# SaLEasyMag.net
KiCad netlist of a schematic drawn in EAGLE
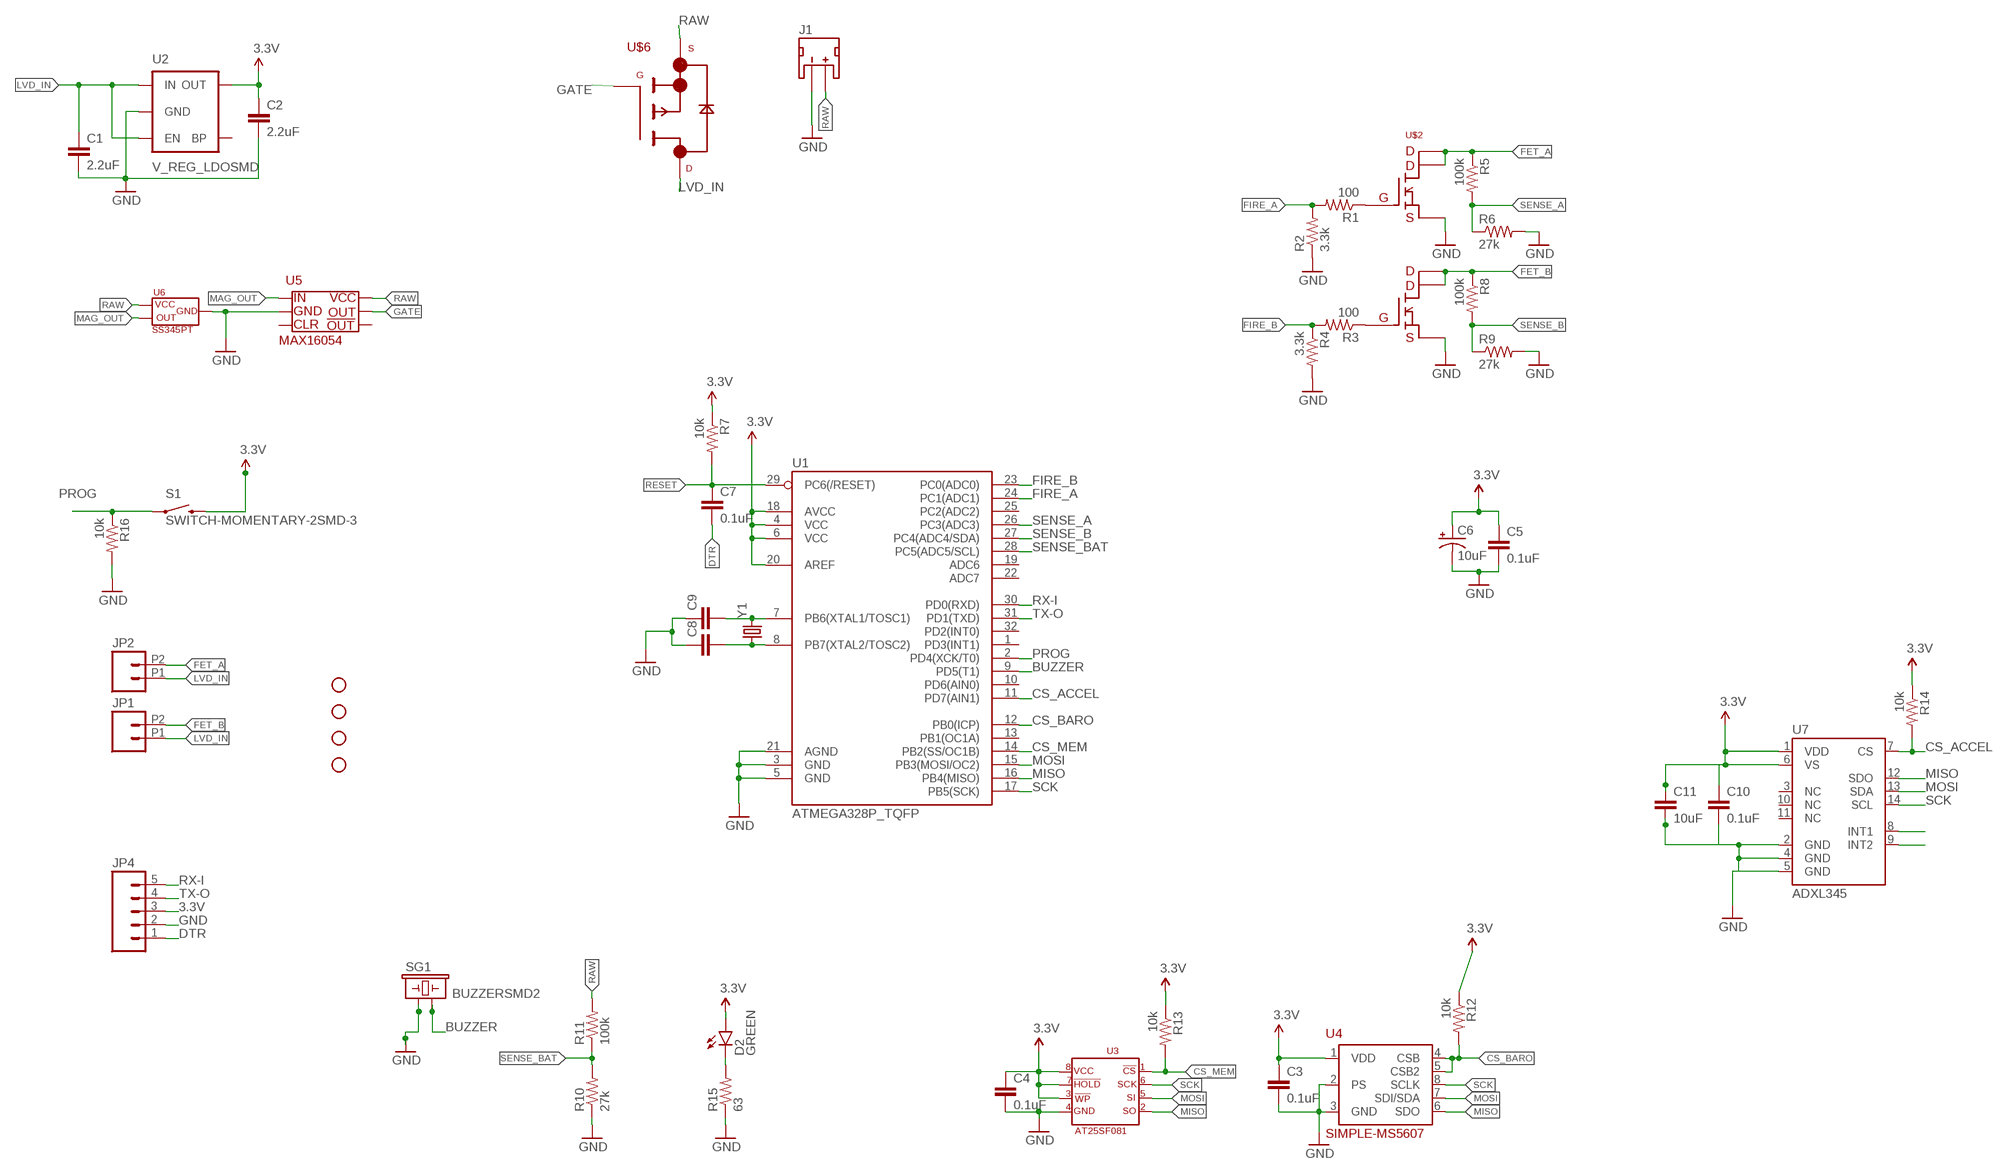
[diagram p0: schematic, sheet 1]

(export (version "E")
  (design (tool "Eeschema 10.0.6"))
  (components
    (comp (ref "C1")
      (value "2.2uF")
      (footprint "eagle-import:0603-CAP")
      (libsource (lib "eagle-import") (part "SparkFun-Passives_CAP0603-CAP"))
    )
    (comp (ref "C2")
      (value "2.2uF")
      (footprint "eagle-import:0603-CAP")
      (libsource (lib "eagle-import") (part "SparkFun-Passives_CAP0603-CAP"))
    )
    (comp (ref "C3")
      (value "0.1uF")
      (footprint "eagle-import:0603-CAP")
      (libsource (lib "eagle-import") (part "SparkFun-Passives_CAP0603-CAP"))
    )
    (comp (ref "C4")
      (value "0.1uF")
      (footprint "eagle-import:0603-CAP")
      (libsource (lib "eagle-import") (part "SparkFun-Passives_CAP0603-CAP"))
    )
    (comp (ref "C5")
      (value "0.1uF")
      (footprint "eagle-import:0603-CAP")
      (libsource (lib "eagle-import") (part "SparkFun-Passives_CAP0603-CAP"))
    )
    (comp (ref "C6")
      (value "10uF")
      (footprint "eagle-import:EIA3216")
      (libsource (lib "eagle-import") (part "CAP_POL1206"))
    )
    (comp (ref "C7")
      (value "0.1uF")
      (footprint "eagle-import:0603-CAP")
      (libsource (lib "eagle-import") (part "SparkFun-Passives_CAP0603-CAP"))
    )
    (comp (ref "C8")
      (value "CAP0402-CAP")
      (footprint "eagle-import:0402-CAP")
      (libsource (lib "eagle-import") (part "CAP0402-CAP"))
    )
    (comp (ref "C9")
      (value "CAP0402-CAP")
      (footprint "eagle-import:0402-CAP")
      (libsource (lib "eagle-import") (part "CAP0402-CAP"))
    )
    (comp (ref "C10")
      (value "0.1uF")
      (footprint "eagle-import:0603-CAP")
      (libsource (lib "eagle-import") (part "SparkFun-Passives_CAP0603-CAP"))
    )
    (comp (ref "C11")
      (value "10uF")
      (footprint "eagle-import:0603-CAP")
      (libsource (lib "eagle-import") (part "SparkFun-Passives_CAP0603-CAP"))
    )
    (comp (ref "D2")
      (value "GREEN")
      (footprint "eagle-import:LED-1206")
      (libsource (lib "eagle-import") (part "LED-GREENLARGE"))
    )
    (comp (ref "J1")
      (value "JST_2MM_MALE")
      (footprint "eagle-import:JST-2-SMD")
      (libsource (lib "eagle-import") (part "JST_2MM_MALE"))
    )
    (comp (ref "JP1")
      (value "M022.54MM_SCREWTERM")
      (footprint "eagle-import:1X02_2.54_SCREWTERM")
      (libsource (lib "eagle-import") (part "M022.54MM_SCREWTERM"))
    )
    (comp (ref "JP2")
      (value "M022.54MM_SCREWTERM")
      (footprint "eagle-import:1X02_2.54_SCREWTERM")
      (libsource (lib "eagle-import") (part "M022.54MM_SCREWTERM"))
    )
    (comp (ref "JP4")
      (value "M05SMD")
      (footprint "eagle-import:1X05-1MM")
      (libsource (lib "eagle-import") (part "M05SMD"))
    )
    (comp (ref "R1")
      (value "100")
      (footprint "eagle-import:0603-RES")
      (libsource (lib "eagle-import") (part "RESISTOR0603-RES"))
    )
    (comp (ref "R2")
      (value "3.3k")
      (footprint "eagle-import:0603-RES")
      (libsource (lib "eagle-import") (part "RESISTOR0603-RES"))
    )
    (comp (ref "R3")
      (value "100")
      (footprint "eagle-import:0603-RES")
      (libsource (lib "eagle-import") (part "RESISTOR0603-RES"))
    )
    (comp (ref "R4")
      (value "3.3k")
      (footprint "eagle-import:0603-RES")
      (libsource (lib "eagle-import") (part "RESISTOR0603-RES"))
    )
    (comp (ref "R5")
      (value "100k")
      (footprint "eagle-import:0603-RES")
      (libsource (lib "eagle-import") (part "RESISTOR0603-RES"))
    )
    (comp (ref "R6")
      (value "27k")
      (footprint "eagle-import:0603-RES")
      (libsource (lib "eagle-import") (part "RESISTOR0603-RES"))
    )
    (comp (ref "R7")
      (value "10k")
      (footprint "eagle-import:0603-RES")
      (libsource (lib "eagle-import") (part "RESISTOR0603-RES"))
    )
    (comp (ref "R8")
      (value "100k")
      (footprint "eagle-import:0603-RES")
      (libsource (lib "eagle-import") (part "RESISTOR0603-RES"))
    )
    (comp (ref "R9")
      (value "27k")
      (footprint "eagle-import:0603-RES")
      (libsource (lib "eagle-import") (part "RESISTOR0603-RES"))
    )
    (comp (ref "R10")
      (value "27k")
      (footprint "eagle-import:0603-RES")
      (libsource (lib "eagle-import") (part "RESISTOR0603-RES"))
    )
    (comp (ref "R11")
      (value "100k")
      (footprint "eagle-import:0603-RES")
      (libsource (lib "eagle-import") (part "RESISTOR0603-RES"))
    )
    (comp (ref "R12")
      (value "10k")
      (footprint "eagle-import:0603-RES")
      (libsource (lib "eagle-import") (part "RESISTOR0603-RES"))
    )
    (comp (ref "R13")
      (value "10k")
      (footprint "eagle-import:0603-RES")
      (libsource (lib "eagle-import") (part "RESISTOR0603-RES"))
    )
    (comp (ref "R14")
      (value "10k")
      (footprint "eagle-import:0603-RES")
      (libsource (lib "eagle-import") (part "RESISTOR0603-RES"))
    )
    (comp (ref "R15")
      (value "63")
      (footprint "eagle-import:0603-RES")
      (libsource (lib "eagle-import") (part "RESISTOR0603-RES"))
    )
    (comp (ref "R16")
      (value "10k")
      (footprint "eagle-import:0603-RES")
      (libsource (lib "eagle-import") (part "RESISTOR0603-RES"))
    )
    (comp (ref "S1")
      (value "SWITCH-MOMENTARY-2SMD-3")
      (footprint "eagle-import:TACTILE_SWITCH_SMD-3")
      (libsource (lib "eagle-import") (part "SWITCH-MOMENTARY-2SMD-3"))
    )
    (comp (ref "SG1")
      (value "BUZZERSMD2")
      (footprint "eagle-import:BUZZER-CCV")
      (libsource (lib "eagle-import") (part "BUZZERSMD2"))
    )
    (comp (ref "STANDOFF1")
      (value "STAND-OFF")
      (footprint "eagle-import:STAND-OFF")
      (libsource (lib "eagle-import") (part "STAND-OFF"))
    )
    (comp (ref "STANDOFF2")
      (value "STAND-OFF")
      (footprint "eagle-import:STAND-OFF")
      (libsource (lib "eagle-import") (part "STAND-OFF"))
    )
    (comp (ref "STANDOFF3")
      (value "STAND-OFF")
      (footprint "eagle-import:STAND-OFF")
      (libsource (lib "eagle-import") (part "STAND-OFF"))
    )
    (comp (ref "STANDOFF4")
      (value "STAND-OFF")
      (footprint "eagle-import:STAND-OFF")
      (libsource (lib "eagle-import") (part "STAND-OFF"))
    )
    (comp (ref "U$2")
      (value "SI7232DN")
      (footprint "eagle-import:SI7232DN")
      (libsource (lib "eagle-import") (part "SI7232DN"))
    )
    (comp (ref "U$6")
      (value "SI7615ADN")
      (footprint "eagle-import:SI7615ADN")
      (libsource (lib "eagle-import") (part "SI7615ADN"))
    )
    (comp (ref "U1")
      (value "ATMEGA328P_TQFP")
      (footprint "eagle-import:TQFP32-08")
      (libsource (lib "eagle-import") (part "ATMEGA328P_TQFP"))
    )
    (comp (ref "U2")
      (value "V_REG_LDOSMD")
      (footprint "eagle-import:SOT23-5")
      (libsource (lib "eagle-import") (part "V_REG_LDOSMD"))
    )
    (comp (ref "U3")
      (value "AT25SF081")
      (footprint "eagle-import:AT25SF081")
      (libsource (lib "eagle-import") (part "AT25SF081"))
    )
    (comp (ref "U4")
      (value "SIMPLE-MS5607")
      (footprint "eagle-import:MS5607")
      (libsource (lib "eagle-import") (part "SIMPLE-MS5607"))
    )
    (comp (ref "U5")
      (value "MAX16054")
      (footprint "eagle-import:MAX16054")
      (libsource (lib "eagle-import") (part "MAX16054"))
    )
    (comp (ref "U6")
      (value "SS345PT")
      (footprint "eagle-import:SS345PT")
      (libsource (lib "eagle-import") (part "SS345PT"))
    )
    (comp (ref "U7")
      (value "ADXL345")
      (footprint "eagle-import:LGA14")
      (libsource (lib "eagle-import") (part "ADXL345"))
    )
    (comp (ref "Y1")
      (value "CRYSTAL5X3")
      (footprint "eagle-import:CRYSTAL-SMD-5X3")
      (libsource (lib "eagle-import") (part "CRYSTAL5X3"))
    )
  )
  (nets
    (net (code "1") (name "/BUZZER") (class "Default")
      (node (ref "SG1") (pin "-") (pinfunction "2_-") (pintype "passive"))
      (node (ref "U1") (pin "9") (pinfunction "PD5(T1)_9") (pintype "bidirectional"))
    )
    (net (code "2") (name "/CS_ACCEL") (class "Default")
      (node (ref "R14") (pin "2") (pinfunction "2_2") (pintype "passive"))
      (node (ref "U1") (pin "11") (pinfunction "PD7(AIN1)_11") (pintype "bidirectional"))
      (node (ref "U7") (pin "7") (pinfunction "CS_7") (pintype "bidirectional"))
    )
    (net (code "3") (name "/PROG") (class "Default")
      (node (ref "R16") (pin "1") (pinfunction "1_1") (pintype "passive"))
      (node (ref "S1") (pin "1") (pinfunction "1_1") (pintype "passive"))
      (node (ref "U1") (pin "2") (pinfunction "PD4(XCK/T0)_2") (pintype "bidirectional"))
    )
    (net (code "4") (name "/RX-I") (class "Default")
      (node (ref "JP4") (pin "5") (pinfunction "5_5") (pintype "passive"))
      (node (ref "U1") (pin "30") (pinfunction "PD0(RXD)_30") (pintype "bidirectional"))
    )
    (net (code "5") (name "/TX-O") (class "Default")
      (node (ref "JP4") (pin "4") (pinfunction "4_4") (pintype "passive"))
      (node (ref "U1") (pin "31") (pinfunction "PD1(TXD)_31") (pintype "bidirectional"))
    )
    (net (code "6") (name "3.3V") (class "Default")
      (node (ref "C10") (pin "1") (pinfunction "1_1") (pintype "passive"))
      (node (ref "C11") (pin "1") (pinfunction "1_1") (pintype "passive"))
      (node (ref "C2") (pin "1") (pinfunction "1_1") (pintype "passive"))
      (node (ref "C3") (pin "1") (pinfunction "1_1") (pintype "passive"))
      (node (ref "C4") (pin "1") (pinfunction "1_1") (pintype "passive"))
      (node (ref "C5") (pin "1") (pinfunction "1_1") (pintype "passive"))
      (node (ref "C6") (pin "A") (pinfunction "+_A") (pintype "passive"))
      (node (ref "D2") (pin "A") (pinfunction "A_A") (pintype "passive"))
      (node (ref "JP4") (pin "3") (pinfunction "3_3") (pintype "passive"))
      (node (ref "R12") (pin "1") (pinfunction "1_1") (pintype "passive"))
      (node (ref "R13") (pin "1") (pinfunction "1_1") (pintype "passive"))
      (node (ref "R14") (pin "1") (pinfunction "1_1") (pintype "passive"))
      (node (ref "R7") (pin "1") (pinfunction "1_1") (pintype "passive"))
      (node (ref "S1") (pin "4") (pinfunction "2_4") (pintype "passive"))
      (node (ref "U1") (pin "18") (pinfunction "AVCC_18") (pintype "bidirectional"))
      (node (ref "U1") (pin "20") (pinfunction "AREF_20") (pintype "bidirectional"))
      (node (ref "U1") (pin "4") (pinfunction "VCC_4") (pintype "bidirectional"))
      (node (ref "U1") (pin "6") (pinfunction "VCC_6") (pintype "bidirectional"))
      (node (ref "U2") (pin "5") (pinfunction "OUT_5") (pintype "passive"))
      (node (ref "U3") (pin "!HOLD") (pinfunction "~{HOLD}_!HOLD") (pintype "bidirectional"))
      (node (ref "U3") (pin "!WP") (pinfunction "~{WP}_!WP") (pintype "bidirectional"))
      (node (ref "U3") (pin "VCC") (pinfunction "VCC_VCC") (pintype "bidirectional"))
      (node (ref "U4") (pin "1") (pinfunction "VDD_1") (pintype "bidirectional"))
      (node (ref "U7") (pin "1") (pinfunction "VDD_1") (pintype "bidirectional"))
      (node (ref "U7") (pin "6") (pinfunction "VS_6") (pintype "bidirectional"))
    )
    (net (code "7") (name "CS_BARO") (class "Default")
      (node (ref "R12") (pin "2") (pinfunction "2_2") (pintype "passive"))
      (node (ref "U1") (pin "12") (pinfunction "PB0(ICP)_12") (pintype "bidirectional"))
      (node (ref "U4") (pin "4") (pinfunction "CSB_4") (pintype "bidirectional"))
      (node (ref "U4") (pin "5") (pinfunction "CSB2_5") (pintype "bidirectional"))
    )
    (net (code "8") (name "CS_MEM") (class "Default")
      (node (ref "R13") (pin "2") (pinfunction "2_2") (pintype "passive"))
      (node (ref "U1") (pin "14") (pinfunction "PB2(SS/OC1B)_14") (pintype "bidirectional"))
      (node (ref "U3") (pin "!CS") (pinfunction "~{CS}_!CS") (pintype "bidirectional"))
    )
    (net (code "9") (name "DTR") (class "Default")
      (node (ref "C7") (pin "2") (pinfunction "2_2") (pintype "passive"))
      (node (ref "JP4") (pin "1") (pinfunction "1_1") (pintype "passive"))
    )
    (net (code "10") (name "FET_A") (class "Default")
      (node (ref "JP2") (pin "P2") (pinfunction "2_P2") (pintype "passive"))
      (node (ref "R5") (pin "1") (pinfunction "1_1") (pintype "passive"))
      (node (ref "U$2") (pin "7") (pinfunction "PIN7_7") (pintype "bidirectional"))
      (node (ref "U$2") (pin "8") (pinfunction "PIN8_8") (pintype "bidirectional"))
    )
    (net (code "11") (name "FET_B") (class "Default")
      (node (ref "JP1") (pin "P2") (pinfunction "2_P2") (pintype "passive"))
      (node (ref "R8") (pin "1") (pinfunction "1_1") (pintype "passive"))
      (node (ref "U$2") (pin "5") (pinfunction "PIN5_5") (pintype "bidirectional"))
      (node (ref "U$2") (pin "6") (pinfunction "PIN6_6") (pintype "bidirectional"))
    )
    (net (code "12") (name "FIRE_A") (class "Default")
      (node (ref "R1") (pin "2") (pinfunction "2_2") (pintype "passive"))
      (node (ref "R2") (pin "2") (pinfunction "2_2") (pintype "passive"))
      (node (ref "U1") (pin "24") (pinfunction "PC1(ADC1)_24") (pintype "bidirectional"))
    )
    (net (code "13") (name "FIRE_B") (class "Default")
      (node (ref "R3") (pin "2") (pinfunction "2_2") (pintype "passive"))
      (node (ref "R4") (pin "1") (pinfunction "1_1") (pintype "passive"))
      (node (ref "U1") (pin "23") (pinfunction "PC0(ADC0)_23") (pintype "bidirectional"))
    )
    (net (code "14") (name "GATE") (class "Default")
      (node (ref "U$6") (pin "G") (pinfunction "G_G") (pintype "bidirectional"))
      (node (ref "U5") (pin "OUT") (pinfunction "OUT_OUT") (pintype "bidirectional"))
    )
    (net (code "15") (name "GND") (class "Default")
      (node (ref "C1") (pin "2") (pinfunction "2_2") (pintype "passive"))
      (node (ref "C10") (pin "2") (pinfunction "2_2") (pintype "passive"))
      (node (ref "C11") (pin "2") (pinfunction "2_2") (pintype "passive"))
      (node (ref "C2") (pin "2") (pinfunction "2_2") (pintype "passive"))
      (node (ref "C3") (pin "2") (pinfunction "2_2") (pintype "passive"))
      (node (ref "C4") (pin "2") (pinfunction "2_2") (pintype "passive"))
      (node (ref "C5") (pin "2") (pinfunction "2_2") (pintype "passive"))
      (node (ref "C6") (pin "C") (pinfunction "-_C") (pintype "passive"))
      (node (ref "C8") (pin "1") (pinfunction "1_1") (pintype "passive"))
      (node (ref "C9") (pin "1") (pinfunction "1_1") (pintype "passive"))
      (node (ref "J1") (pin "1") (pinfunction "-_1") (pintype "bidirectional"))
      (node (ref "JP4") (pin "2") (pinfunction "2_2") (pintype "passive"))
      (node (ref "R10") (pin "1") (pinfunction "1_1") (pintype "passive"))
      (node (ref "R15") (pin "1") (pinfunction "1_1") (pintype "passive"))
      (node (ref "R16") (pin "2") (pinfunction "2_2") (pintype "passive"))
      (node (ref "R2") (pin "1") (pinfunction "1_1") (pintype "passive"))
      (node (ref "R4") (pin "2") (pinfunction "2_2") (pintype "passive"))
      (node (ref "R6") (pin "2") (pinfunction "2_2") (pintype "passive"))
      (node (ref "R9") (pin "2") (pinfunction "2_2") (pintype "passive"))
      (node (ref "SG1") (pin "+") (pinfunction "1_+") (pintype "passive"))
      (node (ref "U$2") (pin "1") (pinfunction "PIN1_1") (pintype "bidirectional"))
      (node (ref "U$2") (pin "3") (pinfunction "PIN3_3") (pintype "bidirectional"))
      (node (ref "U1") (pin "21") (pinfunction "AGND_21") (pintype "bidirectional"))
      (node (ref "U1") (pin "3") (pinfunction "GND_3") (pintype "bidirectional"))
      (node (ref "U1") (pin "5") (pinfunction "GND_5") (pintype "bidirectional"))
      (node (ref "U2") (pin "2") (pinfunction "GND_2") (pintype "input"))
      (node (ref "U3") (pin "GND") (pinfunction "GND_GND") (pintype "bidirectional"))
      (node (ref "U4") (pin "2") (pinfunction "PS_2") (pintype "bidirectional"))
      (node (ref "U4") (pin "3") (pinfunction "GND_3") (pintype "bidirectional"))
      (node (ref "U5") (pin "GND") (pinfunction "GND_GND") (pintype "bidirectional"))
      (node (ref "U6") (pin "GND") (pinfunction "GND_GND") (pintype "bidirectional"))
      (node (ref "U7") (pin "2") (pinfunction "GND_2") (pintype "bidirectional"))
      (node (ref "U7") (pin "4") (pinfunction "GND_4") (pintype "bidirectional"))
      (node (ref "U7") (pin "5") (pinfunction "GND_5") (pintype "bidirectional"))
    )
    (net (code "16") (name "LVD_IN") (class "Default")
      (node (ref "C1") (pin "1") (pinfunction "1_1") (pintype "passive"))
      (node (ref "JP1") (pin "P1") (pinfunction "1_P1") (pintype "passive"))
      (node (ref "JP2") (pin "P1") (pinfunction "1_P1") (pintype "passive"))
      (node (ref "U$6") (pin "D1") (pinfunction "D_D1") (pintype "bidirectional"))
      (node (ref "U$6") (pin "D2") (pinfunction "D_D2") (pintype "bidirectional"))
      (node (ref "U$6") (pin "D3") (pinfunction "D_D3") (pintype "bidirectional"))
      (node (ref "U$6") (pin "D4") (pinfunction "D_D4") (pintype "bidirectional"))
      (node (ref "U2") (pin "1") (pinfunction "IN_1") (pintype "input"))
      (node (ref "U2") (pin "3") (pinfunction "EN_3") (pintype "input"))
    )
    (net (code "17") (name "MAG_OUT") (class "Default")
      (node (ref "U5") (pin "IN") (pinfunction "IN_IN") (pintype "bidirectional"))
      (node (ref "U6") (pin "OUT") (pinfunction "OUT_OUT") (pintype "bidirectional"))
    )
    (net (code "18") (name "MISO") (class "Default")
      (node (ref "U1") (pin "16") (pinfunction "PB4(MISO)_16") (pintype "bidirectional"))
      (node (ref "U3") (pin "SO") (pinfunction "SO_SO") (pintype "bidirectional"))
      (node (ref "U4") (pin "6") (pinfunction "SDO_6") (pintype "bidirectional"))
      (node (ref "U7") (pin "12") (pinfunction "SDO_12") (pintype "bidirectional"))
    )
    (net (code "19") (name "MOSI") (class "Default")
      (node (ref "U1") (pin "15") (pinfunction "PB3(MOSI/OC2)_15") (pintype "bidirectional"))
      (node (ref "U3") (pin "SI") (pinfunction "SI_SI") (pintype "bidirectional"))
      (node (ref "U4") (pin "7") (pinfunction "SDI/SDA_7") (pintype "bidirectional"))
      (node (ref "U7") (pin "13") (pinfunction "SDA_13") (pintype "bidirectional"))
    )
    (net (code "20") (name "Net-(D2-PadC)") (class "Default")
      (node (ref "D2") (pin "C") (pinfunction "C_C") (pintype "passive"))
      (node (ref "R15") (pin "2") (pinfunction "2_2") (pintype "passive"))
    )
    (net (code "21") (name "Net-(U$2-PIN2)") (class "Default")
      (node (ref "R1") (pin "1") (pinfunction "1_1") (pintype "passive"))
      (node (ref "U$2") (pin "2") (pinfunction "PIN2_2") (pintype "bidirectional"))
    )
    (net (code "22") (name "Net-(U$2-PIN4)") (class "Default")
      (node (ref "R3") (pin "1") (pinfunction "1_1") (pintype "passive"))
      (node (ref "U$2") (pin "4") (pinfunction "PIN4_4") (pintype "bidirectional"))
    )
    (net (code "23") (name "Net-(U1-PB6(XTAL1{slash}TOSC1))") (class "Default")
      (node (ref "C9") (pin "2") (pinfunction "2_2") (pintype "passive"))
      (node (ref "U1") (pin "7") (pinfunction "PB6(XTAL1/TOSC1)_7") (pintype "bidirectional"))
      (node (ref "Y1") (pin "3") (pinfunction "2_3") (pintype "passive"))
    )
    (net (code "24") (name "Net-(U1-PB7(XTAL2{slash}TOSC2))") (class "Default")
      (node (ref "C8") (pin "2") (pinfunction "2_2") (pintype "passive"))
      (node (ref "U1") (pin "8") (pinfunction "PB7(XTAL2/TOSC2)_8") (pintype "bidirectional"))
      (node (ref "Y1") (pin "1") (pinfunction "1_1") (pintype "passive"))
    )
    (net (code "25") (name "RAW") (class "Default")
      (node (ref "J1") (pin "2") (pinfunction "+_2") (pintype "bidirectional"))
      (node (ref "R11") (pin "2") (pinfunction "2_2") (pintype "passive"))
      (node (ref "U$6") (pin "S1") (pinfunction "S_S1") (pintype "bidirectional"))
      (node (ref "U$6") (pin "S2") (pinfunction "S_S2") (pintype "bidirectional"))
      (node (ref "U$6") (pin "S3") (pinfunction "S_S3") (pintype "bidirectional"))
      (node (ref "U5") (pin "VCC") (pinfunction "VCC_VCC") (pintype "bidirectional"))
      (node (ref "U6") (pin "VCC") (pinfunction "VCC_VCC") (pintype "bidirectional"))
    )
    (net (code "26") (name "RESET") (class "Default")
      (node (ref "C7") (pin "1") (pinfunction "1_1") (pintype "passive"))
      (node (ref "R7") (pin "2") (pinfunction "2_2") (pintype "passive"))
      (node (ref "U1") (pin "29") (pinfunction "PC6(/RESET)_29") (pintype "bidirectional"))
    )
    (net (code "27") (name "SCK") (class "Default")
      (node (ref "U1") (pin "17") (pinfunction "PB5(SCK)_17") (pintype "bidirectional"))
      (node (ref "U3") (pin "SCK") (pinfunction "SCK_SCK") (pintype "bidirectional"))
      (node (ref "U4") (pin "8") (pinfunction "SCLK_8") (pintype "bidirectional"))
      (node (ref "U7") (pin "14") (pinfunction "SCL_14") (pintype "bidirectional"))
    )
    (net (code "28") (name "SENSE_A") (class "Default")
      (node (ref "R5") (pin "2") (pinfunction "2_2") (pintype "passive"))
      (node (ref "R6") (pin "1") (pinfunction "1_1") (pintype "passive"))
      (node (ref "U1") (pin "26") (pinfunction "PC3(ADC3)_26") (pintype "bidirectional"))
    )
    (net (code "29") (name "SENSE_B") (class "Default")
      (node (ref "R8") (pin "2") (pinfunction "2_2") (pintype "passive"))
      (node (ref "R9") (pin "1") (pinfunction "1_1") (pintype "passive"))
      (node (ref "U1") (pin "27") (pinfunction "PC4(ADC4/SDA)_27") (pintype "bidirectional"))
    )
    (net (code "30") (name "SENSE_BAT") (class "Default")
      (node (ref "R10") (pin "2") (pinfunction "2_2") (pintype "passive"))
      (node (ref "R11") (pin "1") (pinfunction "1_1") (pintype "passive"))
      (node (ref "U1") (pin "28") (pinfunction "PC5(ADC5/SCL)_28") (pintype "bidirectional"))
    )
    (net (code "31") (name "unconnected-(J1-PAD1-PadNC1)") (class "Default")
      (node (ref "J1") (pin "NC1") (pinfunction "PAD1_NC1") (pintype "bidirectional"))
    )
    (net (code "32") (name "unconnected-(J1-PAD2-PadNC2)") (class "Default")
      (node (ref "J1") (pin "NC2") (pinfunction "PAD2_NC2") (pintype "bidirectional"))
    )
    (net (code "33") (name "unconnected-(U1-ADC6-Pad19)") (class "Default")
      (node (ref "U1") (pin "19") (pinfunction "ADC6_19") (pintype "bidirectional"))
    )
    (net (code "34") (name "unconnected-(U1-ADC7-Pad22)") (class "Default")
      (node (ref "U1") (pin "22") (pinfunction "ADC7_22") (pintype "bidirectional"))
    )
    (net (code "35") (name "unconnected-(U1-PB1(OC1A)-Pad13)") (class "Default")
      (node (ref "U1") (pin "13") (pinfunction "PB1(OC1A)_13") (pintype "bidirectional"))
    )
    (net (code "36") (name "unconnected-(U1-PC2(ADC2)-Pad25)") (class "Default")
      (node (ref "U1") (pin "25") (pinfunction "PC2(ADC2)_25") (pintype "bidirectional"))
    )
    (net (code "37") (name "unconnected-(U1-PD2(INT0)-Pad32)") (class "Default")
      (node (ref "U1") (pin "32") (pinfunction "PD2(INT0)_32") (pintype "bidirectional"))
    )
    (net (code "38") (name "unconnected-(U1-PD3(INT1)-Pad1)") (class "Default")
      (node (ref "U1") (pin "1") (pinfunction "PD3(INT1)_1") (pintype "bidirectional"))
    )
    (net (code "39") (name "unconnected-(U1-PD6(AIN0)-Pad10)") (class "Default")
      (node (ref "U1") (pin "10") (pinfunction "PD6(AIN0)_10") (pintype "bidirectional"))
    )
    (net (code "40") (name "unconnected-(U2-BP-Pad4)") (class "Default")
      (node (ref "U2") (pin "4") (pinfunction "BP_4") (pintype "input"))
    )
    (net (code "41") (name "unconnected-(U5-PadCLR)") (class "Default")
      (node (ref "U5") (pin "CLR") (pinfunction "CLR_CLR") (pintype "bidirectional"))
    )
    (net (code "42") (name "unconnected-(U5-~{OUT}-Pad!OUT)") (class "Default")
      (node (ref "U5") (pin "!OUT") (pinfunction "~{OUT}_!OUT") (pintype "bidirectional"))
    )
    (net (code "43") (name "unconnected-(U7-INT1-Pad8)") (class "Default")
      (node (ref "U7") (pin "8") (pinfunction "INT1_8") (pintype "bidirectional"))
    )
    (net (code "44") (name "unconnected-(U7-INT2-Pad9)") (class "Default")
      (node (ref "U7") (pin "9") (pinfunction "INT2_9") (pintype "bidirectional"))
    )
    (net (code "45") (name "unconnected-(U7-NC-Pad3)") (class "Default")
      (node (ref "U7") (pin "3") (pinfunction "NC_3") (pintype "bidirectional"))
    )
    (net (code "46") (name "unconnected-(U7-NC-Pad10)") (class "Default")
      (node (ref "U7") (pin "10") (pinfunction "NC_10") (pintype "bidirectional"))
    )
    (net (code "47") (name "unconnected-(U7-NC-Pad11)") (class "Default")
      (node (ref "U7") (pin "11") (pinfunction "NC_11") (pintype "bidirectional"))
    )
  )
)
